# imas_cjmcu_hx711_ads1232_ads1220.net
KiCad netlist of a schematic drawn in EAGLE
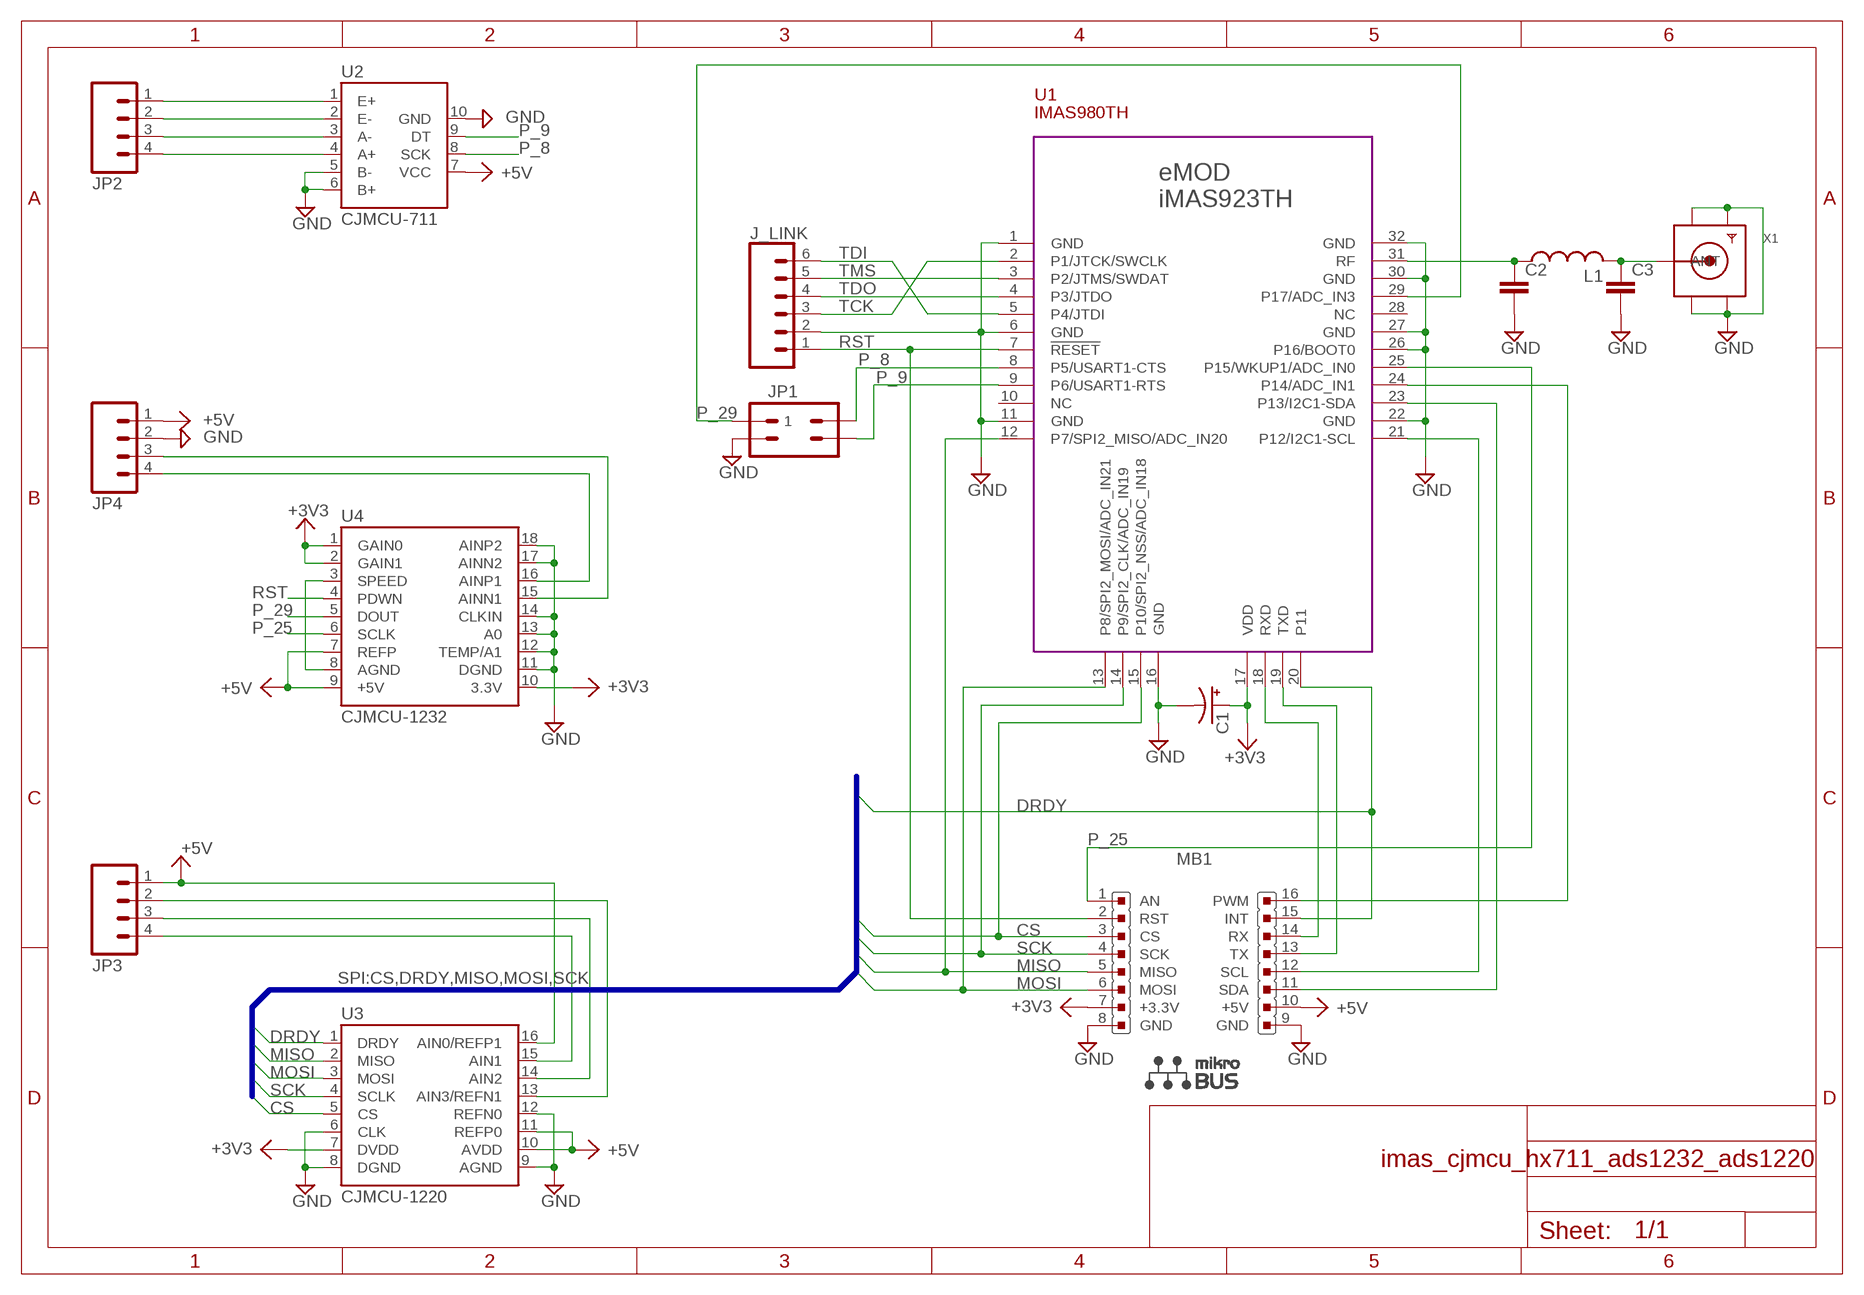
[diagram p0: schematic, sheet 1]

(export (version "E")
  (design (tool "Eeschema 10.0.6"))
  (components
    (comp (ref "C1")
      (value "RCL_CPOL-US085CS-1AW")
      (footprint "eagle-import:RCL_085CS_1AW")
      (libsource (lib "eagle-import") (part "RCL_CPOL-US085CS-1AW"))
    )
    (comp (ref "C2")
      (value "RCL_C-EUC1206")
      (footprint "eagle-import:RCL_C1206")
      (libsource (lib "eagle-import") (part "RCL_C-EUC1206"))
    )
    (comp (ref "C3")
      (value "RCL_C-EUC1206")
      (footprint "eagle-import:RCL_C1206")
      (libsource (lib "eagle-import") (part "RCL_C-EUC1206"))
    )
    (comp (ref "JP1")
      (value "M02X2")
      (footprint "eagle-import:2X02")
      (libsource (lib "eagle-import") (part "M02X2"))
    )
    (comp (ref "JP2")
      (value "M04PTH")
      (footprint "eagle-import:1X04")
      (libsource (lib "eagle-import") (part "M04PTH"))
    )
    (comp (ref "JP3")
      (value "M04PTH")
      (footprint "eagle-import:1X04")
      (libsource (lib "eagle-import") (part "M04PTH"))
    )
    (comp (ref "JP4")
      (value "M04PTH")
      (footprint "eagle-import:1X04")
      (libsource (lib "eagle-import") (part "M04PTH"))
    )
    (comp (ref "J_LINK")
      (value "CONN_06SILK_FEMALE_PTH")
      (footprint "eagle-import:1X06")
      (libsource (lib "eagle-import") (part "CONN_06SILK_FEMALE_PTH"))
    )
    (comp (ref "L1")
      (value "L-USL1812")
      (footprint "eagle-import:L1812")
      (libsource (lib "eagle-import") (part "L-USL1812"))
    )
    (comp (ref "MB1")
      (value "MIKROBUS")
      (footprint "eagle-import:MIKROBUS")
      (libsource (lib "eagle-import") (part "MIKROBUS"))
    )
    (comp (ref "U1")
      (value "IMAS980TH")
      (footprint "eagle-import:IMAS923TH")
      (libsource (lib "eagle-import") (part "IMAS980TH"))
    )
    (comp (ref "U2")
      (value "CJMCU-711")
      (footprint "eagle-import:CJMCU-711")
      (libsource (lib "eagle-import") (part "CJMCU-711"))
    )
    (comp (ref "U3")
      (value "CJMCU-1220")
      (footprint "eagle-import:CJMCU-1220")
      (libsource (lib "eagle-import") (part "CJMCU-1220"))
    )
    (comp (ref "U4")
      (value "CJMCU-1232")
      (footprint "eagle-import:CJMCU-1232")
      (libsource (lib "eagle-import") (part "CJMCU-1232"))
    )
    (comp (ref "X1")
      (value "SMACONNECTOR_EDGE_UFL")
      (footprint "eagle-import:SMA_EDGELAUNCH_UFL")
      (libsource (lib "eagle-import") (part "SMACONNECTOR_EDGE_UFL"))
    )
  )
  (nets
    (net (code "2") (name "+3V3") (class "Default")
      (node (ref "C1") (pin "+") (pinfunction "+_+") (pintype "passive"))
      (node (ref "MB1") (pin "7") (pinfunction "+3.3V_7") (pintype "passive"))
      (node (ref "U1") (pin "17") (pinfunction "VDD_17") (pintype "power_in"))
      (node (ref "U3") (pin "7") (pinfunction "DVDD_7") (pintype "bidirectional"))
      (node (ref "U4") (pin "1") (pinfunction "GAIN0_1") (pintype "bidirectional"))
      (node (ref "U4") (pin "10") (pinfunction "3.3V_10") (pintype "bidirectional"))
      (node (ref "U4") (pin "2") (pinfunction "GAIN1_2") (pintype "bidirectional"))
    )
    (net (code "3") (name "+5V") (class "Default")
      (node (ref "JP3") (pin "1") (pinfunction "1_1") (pintype "passive"))
      (node (ref "JP4") (pin "1") (pinfunction "1_1") (pintype "passive"))
      (node (ref "MB1") (pin "10") (pinfunction "+5V_10") (pintype "passive"))
      (node (ref "U2") (pin "7") (pinfunction "VCC_7") (pintype "bidirectional"))
      (node (ref "U3") (pin "10") (pinfunction "AVDD_10") (pintype "bidirectional"))
      (node (ref "U3") (pin "11") (pinfunction "REFP0_11") (pintype "bidirectional"))
      (node (ref "U3") (pin "16") (pinfunction "AIN0/REFP1_16") (pintype "bidirectional"))
      (node (ref "U4") (pin "7") (pinfunction "REFP_7") (pintype "bidirectional"))
      (node (ref "U4") (pin "9") (pinfunction "+5V_9") (pintype "bidirectional"))
    )
    (net (code "4") (name "/CS") (class "Default")
      (node (ref "MB1") (pin "3") (pinfunction "CS_3") (pintype "bidirectional"))
      (node (ref "U1") (pin "15") (pinfunction "P10/SPI2_NSS/ADC_IN18_15") (pintype "bidirectional"))
      (node (ref "U3") (pin "5") (pinfunction "CS_5") (pintype "bidirectional"))
    )
    (net (code "5") (name "/DRDY") (class "Default")
      (node (ref "MB1") (pin "15") (pinfunction "INT_15") (pintype "bidirectional"))
      (node (ref "U1") (pin "20") (pinfunction "P11_20") (pintype "bidirectional"))
      (node (ref "U3") (pin "1") (pinfunction "DRDY_1") (pintype "bidirectional"))
    )
    (net (code "6") (name "/MISO") (class "Default")
      (node (ref "MB1") (pin "5") (pinfunction "MISO_5") (pintype "bidirectional"))
      (node (ref "U1") (pin "12") (pinfunction "P7/SPI2_MISO/ADC_IN20_12") (pintype "bidirectional"))
      (node (ref "U3") (pin "2") (pinfunction "MISO_2") (pintype "bidirectional"))
    )
    (net (code "7") (name "/MOSI") (class "Default")
      (node (ref "MB1") (pin "6") (pinfunction "MOSI_6") (pintype "bidirectional"))
      (node (ref "U1") (pin "13") (pinfunction "P8/SPI2_MOSI/ADC_IN21_13") (pintype "bidirectional"))
      (node (ref "U3") (pin "3") (pinfunction "MOSI_3") (pintype "bidirectional"))
    )
    (net (code "8") (name "/N$24") (class "Default")
      (node (ref "JP3") (pin "2") (pinfunction "2_2") (pintype "passive"))
      (node (ref "JP3") (pin "3") (pinfunction "3_3") (pintype "passive"))
      (node (ref "JP3") (pin "4") (pinfunction "4_4") (pintype "passive"))
      (node (ref "U3") (pin "13") (pinfunction "AIN3/REFN1_13") (pintype "bidirectional"))
      (node (ref "U3") (pin "14") (pinfunction "AIN2_14") (pintype "bidirectional"))
      (node (ref "U3") (pin "15") (pinfunction "AIN1_15") (pintype "bidirectional"))
    )
    (net (code "9") (name "/P_8") (class "Default")
      (node (ref "JP1") (pin "2") (pinfunction "2_2") (pintype "passive"))
      (node (ref "U1") (pin "8") (pinfunction "P5/USART1-CTS_8") (pintype "bidirectional"))
      (node (ref "U2") (pin "8") (pinfunction "SCK_8") (pintype "bidirectional"))
    )
    (net (code "10") (name "/P_9") (class "Default")
      (node (ref "JP1") (pin "4") (pinfunction "4_4") (pintype "passive"))
      (node (ref "U1") (pin "9") (pinfunction "P6/USART1-RTS_9") (pintype "bidirectional"))
      (node (ref "U2") (pin "9") (pinfunction "DT_9") (pintype "bidirectional"))
    )
    (net (code "11") (name "/P_25") (class "Default")
      (node (ref "MB1") (pin "1") (pinfunction "AN_1") (pintype "bidirectional"))
      (node (ref "U1") (pin "25") (pinfunction "P15/WKUP1/ADC_IN0_25") (pintype "bidirectional"))
      (node (ref "U4") (pin "6") (pinfunction "SCLK_6") (pintype "bidirectional"))
    )
    (net (code "12") (name "/P_29") (class "Default")
      (node (ref "JP1") (pin "1") (pinfunction "1_1") (pintype "passive"))
      (node (ref "U1") (pin "29") (pinfunction "P17/ADC_IN3_29") (pintype "bidirectional"))
      (node (ref "U4") (pin "5") (pinfunction "DOUT_5") (pintype "bidirectional"))
    )
    (net (code "13") (name "/RST") (class "Default")
      (node (ref "J_LINK") (pin "1") (pinfunction "1_1") (pintype "passive"))
      (node (ref "MB1") (pin "2") (pinfunction "RST_2") (pintype "bidirectional"))
      (node (ref "U1") (pin "7") (pinfunction "~{RESET}_7") (pintype "passive"))
      (node (ref "U4") (pin "4") (pinfunction "PDWN_4") (pintype "bidirectional"))
    )
    (net (code "14") (name "/SCK") (class "Default")
      (node (ref "MB1") (pin "4") (pinfunction "SCK_4") (pintype "bidirectional"))
      (node (ref "U1") (pin "14") (pinfunction "P9/SPI2_CLK/ADC_IN19_14") (pintype "bidirectional"))
      (node (ref "U3") (pin "4") (pinfunction "SCLK_4") (pintype "bidirectional"))
    )
    (net (code "15") (name "/TCK") (class "Default")
      (node (ref "J_LINK") (pin "3") (pinfunction "3_3") (pintype "passive"))
      (node (ref "U1") (pin "2") (pinfunction "P1/JTCK/SWCLK_2") (pintype "bidirectional"))
    )
    (net (code "16") (name "/TDI") (class "Default")
      (node (ref "J_LINK") (pin "6") (pinfunction "6_6") (pintype "passive"))
      (node (ref "U1") (pin "5") (pinfunction "P4/JTDI_5") (pintype "bidirectional"))
    )
    (net (code "17") (name "/TDO") (class "Default")
      (node (ref "J_LINK") (pin "4") (pinfunction "4_4") (pintype "passive"))
      (node (ref "U1") (pin "4") (pinfunction "P3/JTDO_4") (pintype "bidirectional"))
    )
    (net (code "18") (name "/TMS") (class "Default")
      (node (ref "J_LINK") (pin "5") (pinfunction "5_5") (pintype "passive"))
      (node (ref "U1") (pin "3") (pinfunction "P2/JTMS/SWDAT_3") (pintype "bidirectional"))
    )
    (net (code "20") (name "GND") (class "Default")
      (node (ref "C1") (pin "-") (pinfunction "-_-") (pintype "passive"))
      (node (ref "C2") (pin "2") (pinfunction "2_2") (pintype "passive"))
      (node (ref "C3") (pin "2") (pinfunction "2_2") (pintype "passive"))
      (node (ref "JP1") (pin "3") (pinfunction "3_3") (pintype "passive"))
      (node (ref "JP4") (pin "2") (pinfunction "2_2") (pintype "passive"))
      (node (ref "J_LINK") (pin "2") (pinfunction "2_2") (pintype "passive"))
      (node (ref "MB1") (pin "8") (pinfunction "GND_8") (pintype "passive"))
      (node (ref "MB1") (pin "9") (pinfunction "GND_9") (pintype "passive"))
      (node (ref "U1") (pin "1") (pinfunction "GND_1") (pintype "power_in"))
      (node (ref "U1") (pin "11") (pinfunction "GND_11") (pintype "power_in"))
      (node (ref "U1") (pin "16") (pinfunction "GND_16") (pintype "power_in"))
      (node (ref "U1") (pin "22") (pinfunction "GND_22") (pintype "power_in"))
      (node (ref "U1") (pin "26") (pinfunction "P16/BOOT0_26") (pintype "passive"))
      (node (ref "U1") (pin "27") (pinfunction "GND_27") (pintype "power_in"))
      (node (ref "U1") (pin "30") (pinfunction "GND_30") (pintype "power_in"))
      (node (ref "U1") (pin "32") (pinfunction "GND_32") (pintype "power_in"))
      (node (ref "U1") (pin "6") (pinfunction "GND_6") (pintype "power_in"))
      (node (ref "U2") (pin "10") (pinfunction "GND_10") (pintype "bidirectional"))
      (node (ref "U2") (pin "5") (pinfunction "B-_5") (pintype "bidirectional"))
      (node (ref "U2") (pin "6") (pinfunction "B+_6") (pintype "bidirectional"))
      (node (ref "U3") (pin "12") (pinfunction "REFN0_12") (pintype "bidirectional"))
      (node (ref "U3") (pin "6") (pinfunction "CLK_6") (pintype "bidirectional"))
      (node (ref "U3") (pin "8") (pinfunction "DGND_8") (pintype "bidirectional"))
      (node (ref "U3") (pin "9") (pinfunction "AGND_9") (pintype "bidirectional"))
      (node (ref "U4") (pin "11") (pinfunction "DGND_11") (pintype "bidirectional"))
      (node (ref "U4") (pin "12") (pinfunction "TEMP/A1_12") (pintype "bidirectional"))
      (node (ref "U4") (pin "13") (pinfunction "A0_13") (pintype "bidirectional"))
      (node (ref "U4") (pin "14") (pinfunction "CLKIN_14") (pintype "bidirectional"))
      (node (ref "U4") (pin "17") (pinfunction "AINN2_17") (pintype "bidirectional"))
      (node (ref "U4") (pin "18") (pinfunction "AINP2_18") (pintype "bidirectional"))
      (node (ref "X1") (pin "GND@1") (pinfunction "GND1_GND@1") (pintype "power_in"))
      (node (ref "X1") (pin "GND@2") (pinfunction "GND2_GND@2") (pintype "power_in"))
      (node (ref "X1") (pin "GND@3") (pinfunction "GND3_GND@3") (pintype "power_in"))
      (node (ref "X1") (pin "GND@4") (pinfunction "GND4_GND@4") (pintype "power_in"))
    )
    (net (code "21") (name "Net-(MB1-PWM)") (class "Default")
      (node (ref "MB1") (pin "16") (pinfunction "PWM_16") (pintype "bidirectional"))
      (node (ref "U1") (pin "24") (pinfunction "P14/ADC_IN1_24") (pintype "bidirectional"))
    )
    (net (code "22") (name "Net-(MB1-RX)") (class "Default")
      (node (ref "MB1") (pin "14") (pinfunction "RX_14") (pintype "bidirectional"))
      (node (ref "U1") (pin "18") (pinfunction "RXD_18") (pintype "bidirectional"))
    )
    (net (code "23") (name "Net-(MB1-SCL)") (class "Default")
      (node (ref "MB1") (pin "12") (pinfunction "SCL_12") (pintype "bidirectional"))
      (node (ref "U1") (pin "21") (pinfunction "P12/I2C1-SCL_21") (pintype "bidirectional"))
    )
    (net (code "24") (name "Net-(MB1-SDA)") (class "Default")
      (node (ref "MB1") (pin "11") (pinfunction "SDA_11") (pintype "bidirectional"))
      (node (ref "U1") (pin "23") (pinfunction "P13/I2C1-SDA_23") (pintype "bidirectional"))
    )
    (net (code "25") (name "Net-(MB1-TX)") (class "Default")
      (node (ref "MB1") (pin "13") (pinfunction "TX_13") (pintype "bidirectional"))
      (node (ref "U1") (pin "19") (pinfunction "TXD_19") (pintype "bidirectional"))
    )
    (net (code "26") (name "Net-(U1-RF)") (class "Default")
      (node (ref "C2") (pin "1") (pinfunction "1_1") (pintype "passive"))
      (node (ref "L1") (pin "1") (pinfunction "1_1") (pintype "passive"))
      (node (ref "U1") (pin "31") (pinfunction "RF_31") (pintype "bidirectional"))
    )
    (net (code "27") (name "Net-(U2-A+)") (class "Default")
      (node (ref "JP2") (pin "4") (pinfunction "4_4") (pintype "passive"))
      (node (ref "U2") (pin "4") (pinfunction "A+_4") (pintype "bidirectional"))
    )
    (net (code "28") (name "Net-(U2-A-)") (class "Default")
      (node (ref "JP2") (pin "3") (pinfunction "3_3") (pintype "passive"))
      (node (ref "U2") (pin "3") (pinfunction "A-_3") (pintype "bidirectional"))
    )
    (net (code "29") (name "Net-(U2-E+)") (class "Default")
      (node (ref "JP2") (pin "1") (pinfunction "1_1") (pintype "passive"))
      (node (ref "U2") (pin "1") (pinfunction "E+_1") (pintype "bidirectional"))
    )
    (net (code "30") (name "Net-(U2-E-)") (class "Default")
      (node (ref "JP2") (pin "2") (pinfunction "2_2") (pintype "passive"))
      (node (ref "U2") (pin "2") (pinfunction "E-_2") (pintype "bidirectional"))
    )
    (net (code "31") (name "Net-(U4-AGND)") (class "Default")
      (node (ref "U4") (pin "3") (pinfunction "SPEED_3") (pintype "bidirectional"))
      (node (ref "U4") (pin "8") (pinfunction "AGND_8") (pintype "bidirectional"))
    )
    (net (code "32") (name "Net-(U4-AINN1)") (class "Default")
      (node (ref "JP4") (pin "3") (pinfunction "3_3") (pintype "passive"))
      (node (ref "U4") (pin "15") (pinfunction "AINN1_15") (pintype "bidirectional"))
    )
    (net (code "33") (name "Net-(U4-AINP1)") (class "Default")
      (node (ref "JP4") (pin "4") (pinfunction "4_4") (pintype "passive"))
      (node (ref "U4") (pin "16") (pinfunction "AINP1_16") (pintype "bidirectional"))
    )
    (net (code "34") (name "Net-(X1-ANT)") (class "Default")
      (node (ref "C3") (pin "1") (pinfunction "1_1") (pintype "passive"))
      (node (ref "L1") (pin "2") (pinfunction "2_2") (pintype "passive"))
      (node (ref "X1") (pin "P") (pinfunction "ANT_P") (pintype "bidirectional"))
    )
    (net (code "35") (name "unconnected-(U1-NC-Pad10)") (class "Default")
      (node (ref "U1") (pin "10") (pinfunction "NC_10") (pintype "no_connect"))
    )
    (net (code "36") (name "unconnected-(U1-NC-Pad28)") (class "Default")
      (node (ref "U1") (pin "28") (pinfunction "NC_28") (pintype "no_connect"))
    )
  )
)
